# 555_556_Tester.net
KiCad netlist of a schematic drawn in EAGLE
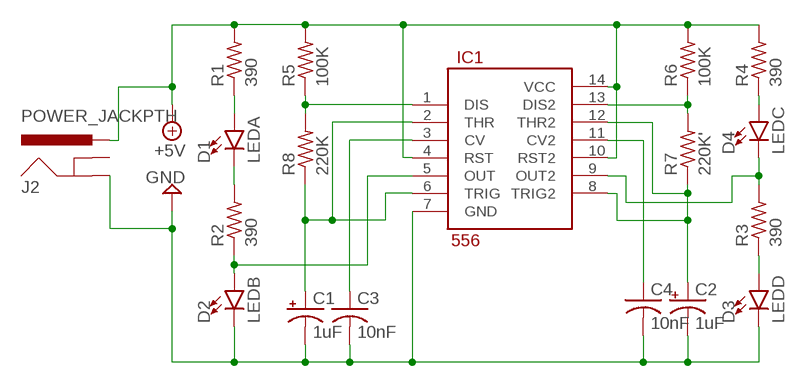
[diagram p0: schematic, sheet 1]

(export (version "E")
  (design (tool "Eeschema 10.0.6"))
  (components
    (comp (ref "C1")
      (value "1uF")
      (footprint "eagle-import:E2-4")
      (libsource (lib "eagle-import") (part "CPOL-USE2-4"))
    )
    (comp (ref "C2")
      (value "1uF")
      (footprint "eagle-import:E2-4")
      (libsource (lib "eagle-import") (part "CPOL-USE2-4"))
    )
    (comp (ref "C3")
      (value "10nF")
      (footprint "eagle-import:C025-025X050")
      (libsource (lib "eagle-import") (part "C-US025-025X050"))
    )
    (comp (ref "C4")
      (value "10nF")
      (footprint "eagle-import:C025-025X050")
      (libsource (lib "eagle-import") (part "C-US025-025X050"))
    )
    (comp (ref "D1")
      (value "LEDA")
      (footprint "eagle-import:LED_3MM")
      (libsource (lib "eagle-import") (part "LED3MM"))
    )
    (comp (ref "D2")
      (value "LEDB")
      (footprint "eagle-import:LED_3MM")
      (libsource (lib "eagle-import") (part "LED3MM"))
    )
    (comp (ref "D3")
      (value "LEDD")
      (footprint "eagle-import:LED_3MM")
      (libsource (lib "eagle-import") (part "LED3MM"))
    )
    (comp (ref "D4")
      (value "LEDC")
      (footprint "eagle-import:LED_3MM")
      (libsource (lib "eagle-import") (part "LED3MM"))
    )
    (comp (ref "IC1")
      (value "556")
      (footprint "eagle-import:DIL14-KIT")
      (libsource (lib "eagle-import") (part "556KIT"))
    )
    (comp (ref "J2")
      (value "POWER_JACKPTH")
      (footprint "eagle-import:POWER_JACK_PTH")
      (libsource (lib "eagle-import") (part "POWER_JACKPTH"))
    )
    (comp (ref "R1")
      (value "390")
      (footprint "eagle-import:0204_5")
      (libsource (lib "eagle-import") (part "R-US_0204/5"))
    )
    (comp (ref "R2")
      (value "390")
      (footprint "eagle-import:0204_5")
      (libsource (lib "eagle-import") (part "R-US_0204/5"))
    )
    (comp (ref "R3")
      (value "390")
      (footprint "eagle-import:0204_5")
      (libsource (lib "eagle-import") (part "R-US_0204/5"))
    )
    (comp (ref "R4")
      (value "390")
      (footprint "eagle-import:0204_5")
      (libsource (lib "eagle-import") (part "R-US_0204/5"))
    )
    (comp (ref "R5")
      (value "100K")
      (footprint "eagle-import:0204_5")
      (libsource (lib "eagle-import") (part "R-US_0204/5"))
    )
    (comp (ref "R6")
      (value "100K")
      (footprint "eagle-import:0204_5")
      (libsource (lib "eagle-import") (part "R-US_0204/5"))
    )
    (comp (ref "R7")
      (value "220K'")
      (footprint "eagle-import:0204_5")
      (libsource (lib "eagle-import") (part "R-US_0204/5"))
    )
    (comp (ref "R8")
      (value "220K")
      (footprint "eagle-import:0204_5")
      (libsource (lib "eagle-import") (part "R-US_0204/5"))
    )
  )
  (nets
    (net (code "1") (name "+5V") (class "Default")
      (node (ref "IC1") (pin "10") (pinfunction "RST2_10") (pintype "bidirectional"))
      (node (ref "IC1") (pin "14") (pinfunction "VCC_14") (pintype "bidirectional"))
      (node (ref "IC1") (pin "4") (pinfunction "RST_4") (pintype "bidirectional"))
      (node (ref "J2") (pin "PWR") (pinfunction "PWR_PWR") (pintype "bidirectional"))
      (node (ref "R1") (pin "2") (pinfunction "2_2") (pintype "passive"))
      (node (ref "R4") (pin "2") (pinfunction "2_2") (pintype "passive"))
      (node (ref "R5") (pin "2") (pinfunction "2_2") (pintype "passive"))
      (node (ref "R6") (pin "2") (pinfunction "2_2") (pintype "passive"))
    )
    (net (code "2") (name "GND") (class "Default")
      (node (ref "C1") (pin "-") (pinfunction "-_-") (pintype "passive"))
      (node (ref "C2") (pin "-") (pinfunction "-_-") (pintype "passive"))
      (node (ref "C3") (pin "2") (pinfunction "2_2") (pintype "passive"))
      (node (ref "C4") (pin "2") (pinfunction "2_2") (pintype "passive"))
      (node (ref "D2") (pin "K") (pinfunction "C_K") (pintype "passive"))
      (node (ref "D3") (pin "K") (pinfunction "C_K") (pintype "passive"))
      (node (ref "IC1") (pin "7") (pinfunction "GND_7") (pintype "bidirectional"))
      (node (ref "J2") (pin "GND") (pinfunction "GND_GND") (pintype "bidirectional"))
    )
    (net (code "3") (name "Net-(D1-C)") (class "Default")
      (node (ref "D1") (pin "K") (pinfunction "C_K") (pintype "passive"))
      (node (ref "R2") (pin "2") (pinfunction "2_2") (pintype "passive"))
    )
    (net (code "4") (name "Net-(D1-PadA)") (class "Default")
      (node (ref "D1") (pin "A") (pinfunction "A_A") (pintype "passive"))
      (node (ref "R1") (pin "1") (pinfunction "1_1") (pintype "passive"))
    )
    (net (code "5") (name "Net-(D3-PadA)") (class "Default")
      (node (ref "D3") (pin "A") (pinfunction "A_A") (pintype "passive"))
      (node (ref "R3") (pin "1") (pinfunction "1_1") (pintype "passive"))
    )
    (net (code "6") (name "Net-(D4-C)") (class "Default")
      (node (ref "D4") (pin "K") (pinfunction "C_K") (pintype "passive"))
      (node (ref "IC1") (pin "9") (pinfunction "OUT2_9") (pintype "bidirectional"))
      (node (ref "R3") (pin "2") (pinfunction "2_2") (pintype "passive"))
    )
    (net (code "7") (name "Net-(D4-PadA)") (class "Default")
      (node (ref "D4") (pin "A") (pinfunction "A_A") (pintype "passive"))
      (node (ref "R4") (pin "1") (pinfunction "1_1") (pintype "passive"))
    )
    (net (code "8") (name "Net-(IC1-CV)") (class "Default")
      (node (ref "C3") (pin "1") (pinfunction "1_1") (pintype "passive"))
      (node (ref "IC1") (pin "3") (pinfunction "CV_3") (pintype "bidirectional"))
    )
    (net (code "9") (name "Net-(IC1-CV2)") (class "Default")
      (node (ref "C4") (pin "1") (pinfunction "1_1") (pintype "passive"))
      (node (ref "IC1") (pin "11") (pinfunction "CV2_11") (pintype "bidirectional"))
    )
    (net (code "10") (name "Net-(IC1-DIS)") (class "Default")
      (node (ref "IC1") (pin "1") (pinfunction "DIS_1") (pintype "bidirectional"))
      (node (ref "R5") (pin "1") (pinfunction "1_1") (pintype "passive"))
      (node (ref "R8") (pin "2") (pinfunction "2_2") (pintype "passive"))
    )
    (net (code "11") (name "Net-(IC1-DIS2)") (class "Default")
      (node (ref "IC1") (pin "13") (pinfunction "DIS2_13") (pintype "bidirectional"))
      (node (ref "R6") (pin "1") (pinfunction "1_1") (pintype "passive"))
      (node (ref "R7") (pin "2") (pinfunction "2_2") (pintype "passive"))
    )
    (net (code "12") (name "Net-(IC1-OUT)") (class "Default")
      (node (ref "D2") (pin "A") (pinfunction "A_A") (pintype "passive"))
      (node (ref "IC1") (pin "5") (pinfunction "OUT_5") (pintype "bidirectional"))
      (node (ref "R2") (pin "1") (pinfunction "1_1") (pintype "passive"))
    )
    (net (code "13") (name "Net-(IC1-THR)") (class "Default")
      (node (ref "C1") (pin "+") (pinfunction "+_+") (pintype "passive"))
      (node (ref "IC1") (pin "2") (pinfunction "THR_2") (pintype "bidirectional"))
      (node (ref "IC1") (pin "6") (pinfunction "TRIG_6") (pintype "bidirectional"))
      (node (ref "R8") (pin "1") (pinfunction "1_1") (pintype "passive"))
    )
    (net (code "14") (name "Net-(IC1-THR2)") (class "Default")
      (node (ref "C2") (pin "+") (pinfunction "+_+") (pintype "passive"))
      (node (ref "IC1") (pin "12") (pinfunction "THR2_12") (pintype "bidirectional"))
      (node (ref "IC1") (pin "8") (pinfunction "TRIG2_8") (pintype "bidirectional"))
      (node (ref "R7") (pin "1") (pinfunction "1_1") (pintype "passive"))
    )
    (net (code "15") (name "unconnected-(J2-PadGNDBREAK)") (class "Default")
      (node (ref "J2") (pin "GNDBREAK") (pinfunction "GNDBREAK_GNDBREAK") (pintype "bidirectional"))
    )
  )
)
